# laser_driver.net
KiCad netlist of a schematic drawn in EAGLE
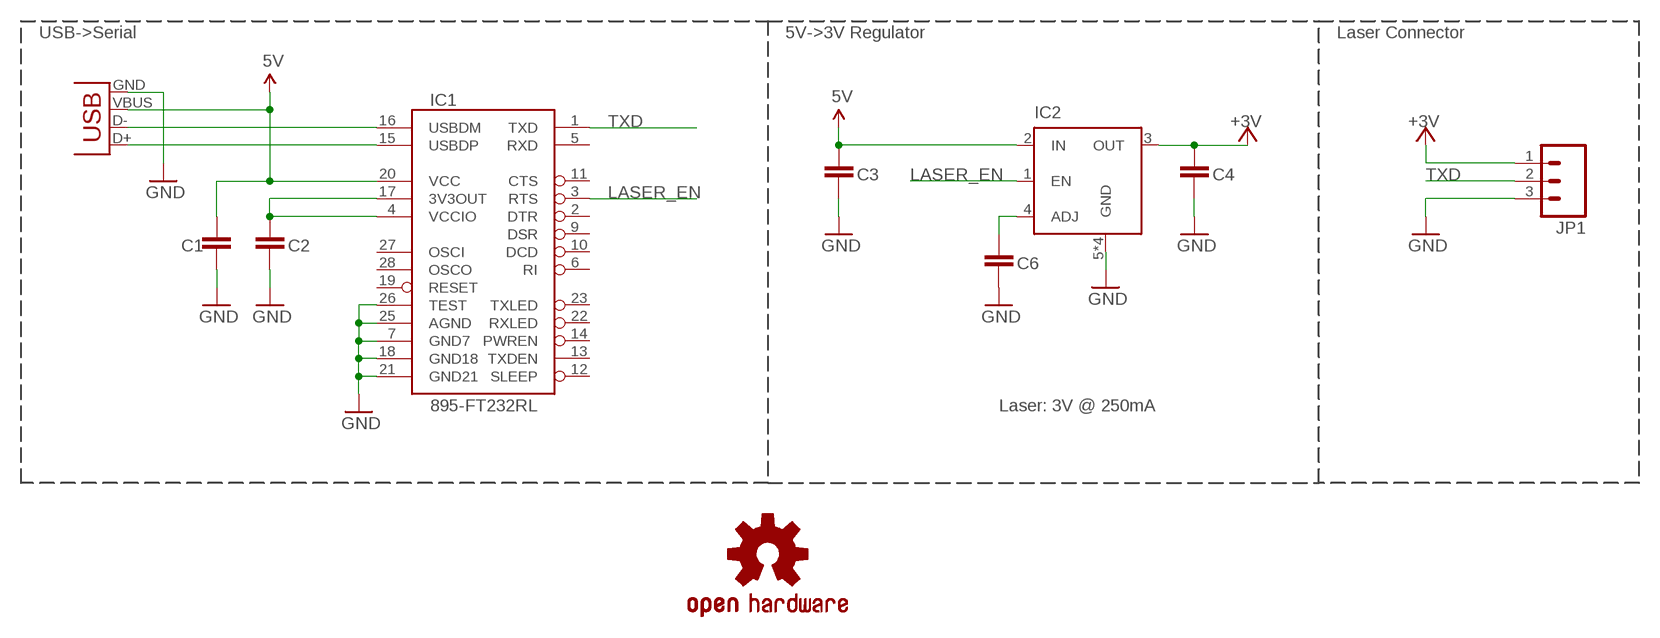
[diagram p0: schematic, sheet 1]

(export (version "E")
  (design (tool "Eeschema 10.0.6"))
  (components
    (comp (ref "C1")
      (value "C1608X5R1C106M080AB")
      (footprint "eagle-import:0603-CAP")
      (libsource (lib "eagle-import") (part "CAP0603-CAP"))
    )
    (comp (ref "C2")
      (value "C1608X5R1C106M080AB")
      (footprint "eagle-import:0603-CAP")
      (libsource (lib "eagle-import") (part "CAP0603-CAP"))
    )
    (comp (ref "C3")
      (value "C1608X5R1C106M080AB")
      (footprint "eagle-import:0603-CAP")
      (libsource (lib "eagle-import") (part "SparkFun-Passives_CAP0603-CAP"))
    )
    (comp (ref "C4")
      (value "C1608X5R1C106M080AB")
      (footprint "eagle-import:0603-CAP")
      (libsource (lib "eagle-import") (part "SparkFun-Passives_CAP0603-CAP"))
    )
    (comp (ref "C6")
      (value "VJ0603A471KXQPW1BC")
      (footprint "eagle-import:0603-CAP")
      (libsource (lib "eagle-import") (part "SparkFun-Passives_CAP0603-CAP"))
    )
    (comp (ref "IC1")
      (value "895-FT232RL")
      (footprint "eagle-import:SSOP28DB")
      (libsource (lib "eagle-import") (part "FT232RLSSOP"))
    )
    (comp (ref "IC2")
      (value "998-MIC5219-3.0YMM")
      (footprint "eagle-import:MSOP08")
      (fields (field (name "MF") "ALTERA CORPORATION") (field (name "MPN") "MIC5219BMM"))
      (libsource (lib "eagle-import") (part "MIC5219BMM"))
    )
    (comp (ref "JP1")
      (value "651-5442251")
      (footprint "eagle-import:SCREWTERMINAL-3.5MM-3")
      (libsource (lib "eagle-import") (part "M03SCREW"))
    )
    (comp (ref "LOGO1")
      (value "OSHW-LOGOS")
      (footprint "eagle-import:OSHW-LOGO-S")
      (libsource (lib "eagle-import") (part "OSHW-LOGOS"))
    )
    (comp (ref "X1")
      (value "798-ZX62RD-AB-5P8")
      (footprint "eagle-import:USB-MICROB")
      (libsource (lib "eagle-import") (part "USB-MICROB"))
    )
  )
  (nets
    (net (code "1") (name "+3V") (class "Default")
      (node (ref "C4") (pin "1") (pinfunction "1_1") (pintype "passive"))
      (node (ref "IC2") (pin "3") (pinfunction "OUT_3") (pintype "output"))
      (node (ref "JP1") (pin "1") (pinfunction "1_1") (pintype "passive"))
    )
    (net (code "2") (name "/LASER_EN") (class "Default")
      (node (ref "IC1") (pin "3") (pinfunction "RTS_3") (pintype "output"))
      (node (ref "IC2") (pin "1") (pinfunction "EN_1") (pintype "input"))
    )
    (net (code "3") (name "/TXD") (class "Default")
      (node (ref "IC1") (pin "1") (pinfunction "TXD_1") (pintype "output"))
      (node (ref "JP1") (pin "2") (pinfunction "2_2") (pintype "passive"))
    )
    (net (code "4") (name "5V") (class "Default")
      (node (ref "C1") (pin "1") (pinfunction "1_1") (pintype "passive"))
      (node (ref "C3") (pin "1") (pinfunction "1_1") (pintype "passive"))
      (node (ref "IC1") (pin "20") (pinfunction "VCC_20") (pintype "power_in"))
      (node (ref "IC2") (pin "2") (pinfunction "IN_2") (pintype "input"))
      (node (ref "X1") (pin "VBUS") (pinfunction "VBUS_VBUS") (pintype "bidirectional"))
    )
    (net (code "5") (name "GND") (class "Default")
      (node (ref "C1") (pin "2") (pinfunction "2_2") (pintype "passive"))
      (node (ref "C2") (pin "2") (pinfunction "2_2") (pintype "passive"))
      (node (ref "C3") (pin "2") (pinfunction "2_2") (pintype "passive"))
      (node (ref "C4") (pin "2") (pinfunction "2_2") (pintype "passive"))
      (node (ref "C6") (pin "2") (pinfunction "2_2") (pintype "passive"))
      (node (ref "IC1") (pin "18") (pinfunction "GND18_18") (pintype "power_in"))
      (node (ref "IC1") (pin "21") (pinfunction "GND21_21") (pintype "power_in"))
      (node (ref "IC1") (pin "25") (pinfunction "AGND_25") (pintype "power_in"))
      (node (ref "IC1") (pin "26") (pinfunction "TEST_26") (pintype "input"))
      (node (ref "IC1") (pin "7") (pinfunction "GND7_7") (pintype "power_in"))
      (node (ref "IC2") (pin "5") (pinfunction "GND_5") (pintype "power_in"))
      (node (ref "IC2") (pin "6") (pinfunction "GND_6") (pintype "power_in"))
      (node (ref "IC2") (pin "7") (pinfunction "GND_7") (pintype "power_in"))
      (node (ref "IC2") (pin "8") (pinfunction "GND_8") (pintype "power_in"))
      (node (ref "JP1") (pin "3") (pinfunction "3_3") (pintype "passive"))
      (node (ref "X1") (pin "GND") (pinfunction "GND_GND") (pintype "bidirectional"))
    )
    (net (code "6") (name "Net-(IC1-3V3OUT)") (class "Default")
      (node (ref "C2") (pin "1") (pinfunction "1_1") (pintype "passive"))
      (node (ref "IC1") (pin "17") (pinfunction "3V3OUT_17") (pintype "output"))
      (node (ref "IC1") (pin "4") (pinfunction "VCCIO_4") (pintype "power_in"))
    )
    (net (code "7") (name "Net-(IC1-USBDM)") (class "Default")
      (node (ref "IC1") (pin "16") (pinfunction "USBDM_16") (pintype "bidirectional"))
      (node (ref "X1") (pin "D-") (pinfunction "D-_D-") (pintype "bidirectional"))
    )
    (net (code "8") (name "Net-(IC1-USBDP)") (class "Default")
      (node (ref "IC1") (pin "15") (pinfunction "USBDP_15") (pintype "bidirectional"))
      (node (ref "X1") (pin "D+") (pinfunction "D+_D+") (pintype "bidirectional"))
    )
    (net (code "9") (name "Net-(IC2-ADJ)") (class "Default")
      (node (ref "C6") (pin "1") (pinfunction "1_1") (pintype "passive"))
      (node (ref "IC2") (pin "4") (pinfunction "ADJ_4") (pintype "passive"))
    )
    (net (code "10") (name "unconnected-(IC1-CTS-Pad11)") (class "Default")
      (node (ref "IC1") (pin "11") (pinfunction "CTS_11") (pintype "input"))
    )
    (net (code "11") (name "unconnected-(IC1-DCD-Pad10)") (class "Default")
      (node (ref "IC1") (pin "10") (pinfunction "DCD_10") (pintype "input"))
    )
    (net (code "12") (name "unconnected-(IC1-DSR-Pad9)") (class "Default")
      (node (ref "IC1") (pin "9") (pinfunction "DSR_9") (pintype "input"))
    )
    (net (code "13") (name "unconnected-(IC1-DTR-Pad2)") (class "Default")
      (node (ref "IC1") (pin "2") (pinfunction "DTR_2") (pintype "output"))
    )
    (net (code "14") (name "unconnected-(IC1-OSCI-Pad27)") (class "Default")
      (node (ref "IC1") (pin "27") (pinfunction "OSCI_27") (pintype "input"))
    )
    (net (code "15") (name "unconnected-(IC1-OSCO-Pad28)") (class "Default")
      (node (ref "IC1") (pin "28") (pinfunction "OSCO_28") (pintype "output"))
    )
    (net (code "16") (name "unconnected-(IC1-PWREN-Pad14)") (class "Default")
      (node (ref "IC1") (pin "14") (pinfunction "PWREN_14") (pintype "input"))
    )
    (net (code "17") (name "unconnected-(IC1-RESET-Pad19)") (class "Default")
      (node (ref "IC1") (pin "19") (pinfunction "RESET_19") (pintype "input"))
    )
    (net (code "18") (name "unconnected-(IC1-RI-Pad6)") (class "Default")
      (node (ref "IC1") (pin "6") (pinfunction "RI_6") (pintype "input"))
    )
    (net (code "19") (name "unconnected-(IC1-RXD-Pad5)") (class "Default")
      (node (ref "IC1") (pin "5") (pinfunction "RXD_5") (pintype "input"))
    )
    (net (code "20") (name "unconnected-(IC1-RXLED-Pad22)") (class "Default")
      (node (ref "IC1") (pin "22") (pinfunction "RXLED_22") (pintype "input"))
    )
    (net (code "21") (name "unconnected-(IC1-SLEEP-Pad12)") (class "Default")
      (node (ref "IC1") (pin "12") (pinfunction "SLEEP_12") (pintype "input"))
    )
    (net (code "22") (name "unconnected-(IC1-TXDEN-Pad13)") (class "Default")
      (node (ref "IC1") (pin "13") (pinfunction "TXDEN_13") (pintype "input"))
    )
    (net (code "23") (name "unconnected-(IC1-TXLED-Pad23)") (class "Default")
      (node (ref "IC1") (pin "23") (pinfunction "TXLED_23") (pintype "input"))
    )
  )
)
